# vs1003.net
KiCad netlist of a schematic drawn in Altium Designer
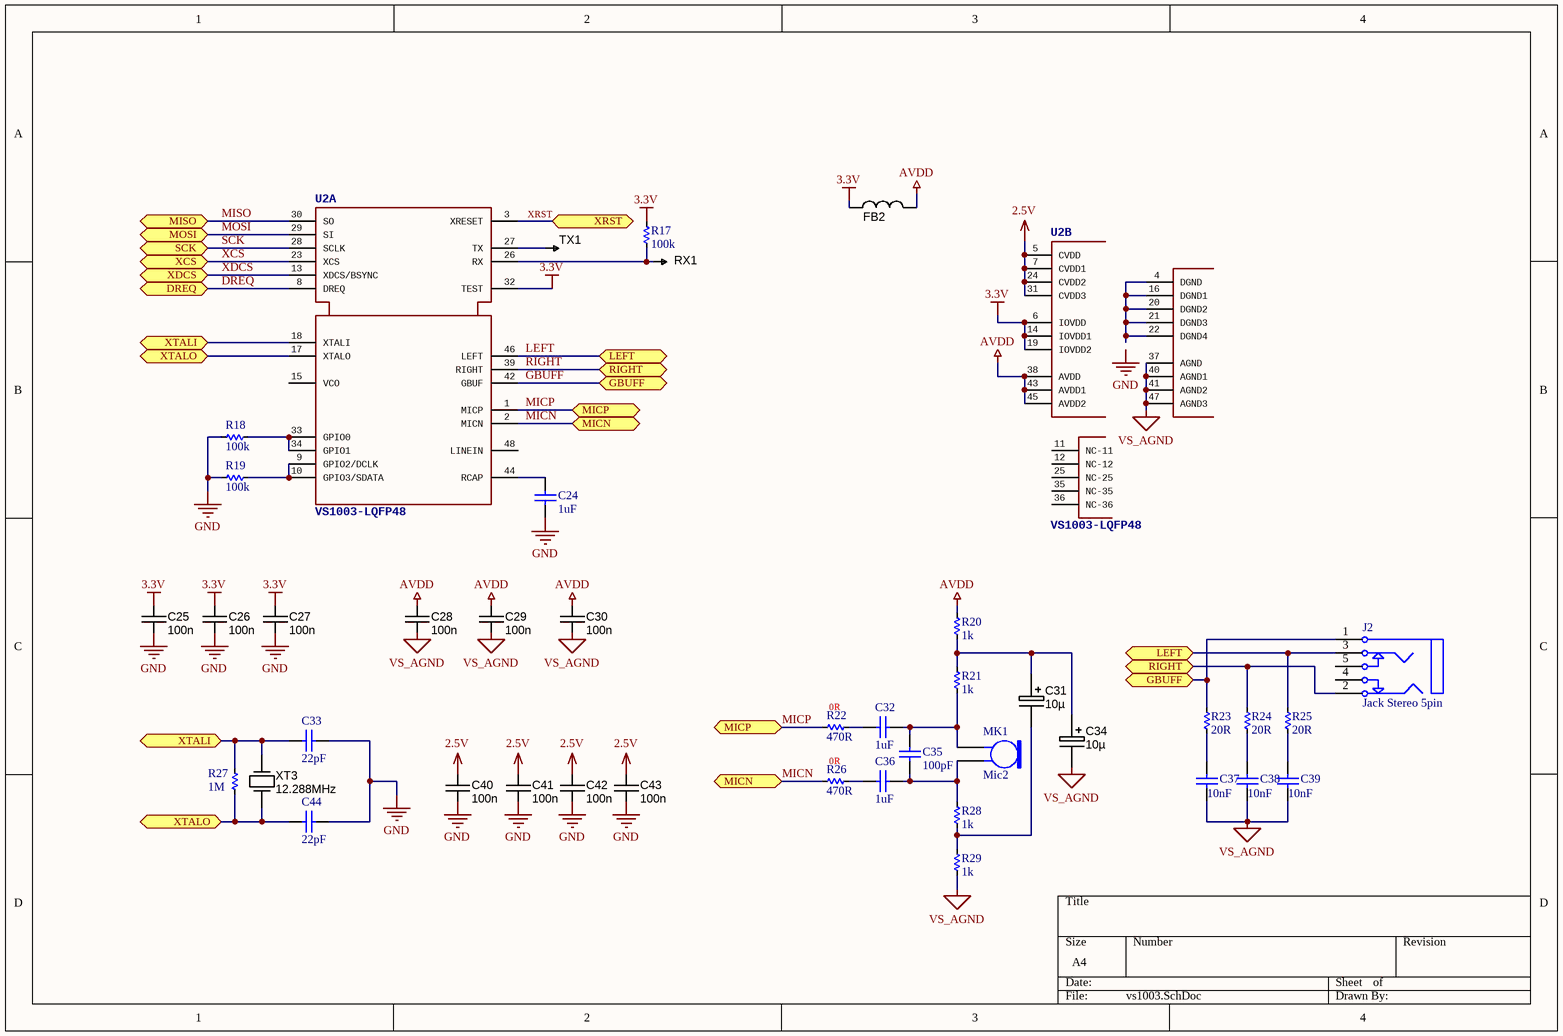
[diagram p0: vs1003.SchDoc]

(export (version "E")
  (design (tool "Eeschema 10.0.6"))
  (components
    (comp (ref "C24")
      (value "1uF")
      (footprint "C0805")
      (description "Capacitor (Semiconductor SIM Model)")
      (fields (field (name "Comment") "Cap Semi") (field (name "PUBLISHER") "Altium Limited"))
      (libsource (lib "Mylib") (part "Cap Semi"))
    )
    (comp (ref "C25")
      (value "100n")
      (footprint "CAPC1608X90N")
      (description "Capacitor SMD Cer 100nF 10% 50V X7R 0603")
      (fields (field (name "TOLERANCE") "±10%") (field (name "Comment") "approved sub OK"))
      (libsource (lib "PBL - Capacitors") (part "CAPC_100n_0603_X7R_50V_10%"))
    )
    (comp (ref "C26")
      (value "100n")
      (footprint "CAPC1608X90N")
      (description "Capacitor SMD Cer 100nF 10% 50V X7R 0603")
      (fields (field (name "TOLERANCE") "±10%") (field (name "Comment") "approved sub OK"))
      (libsource (lib "PBL - Capacitors") (part "CAPC_100n_0603_X7R_50V_10%"))
    )
    (comp (ref "C27")
      (value "100n")
      (footprint "CAPC1608X90N")
      (description "Capacitor SMD Cer 100nF 10% 50V X7R 0603")
      (fields (field (name "TOLERANCE") "±10%") (field (name "Comment") "approved sub OK"))
      (libsource (lib "PBL - Capacitors") (part "CAPC_100n_0603_X7R_50V_10%"))
    )
    (comp (ref "C28")
      (value "100n")
      (footprint "CAPC1608X90N")
      (description "Capacitor SMD Cer 100nF 10% 50V X7R 0603")
      (fields (field (name "TOLERANCE") "±10%") (field (name "Comment") "approved sub OK"))
      (libsource (lib "PBL - Capacitors") (part "CAPC_100n_0603_X7R_50V_10%"))
    )
    (comp (ref "C29")
      (value "100n")
      (footprint "CAPC1608X90N")
      (description "Capacitor SMD Cer 100nF 10% 50V X7R 0603")
      (fields (field (name "TOLERANCE") "±10%") (field (name "Comment") "approved sub OK"))
      (libsource (lib "PBL - Capacitors") (part "CAPC_100n_0603_X7R_50V_10%"))
    )
    (comp (ref "C30")
      (value "100n")
      (footprint "CAPC1608X90N")
      (description "Capacitor SMD Cer 100nF 10% 50V X7R 0603")
      (fields (field (name "TOLERANCE") "±10%") (field (name "Comment") "approved sub OK"))
      (libsource (lib "PBL - Capacitors") (part "CAPC_100n_0603_X7R_50V_10%"))
    )
    (comp (ref "C31")
      (value "10µ")
      (footprint "CAPMP3216X180N")
      (description "Capacitor SMD Tantalum 68uF 10% 6.3V EIA 3216-18")
      (fields (field (name "TOLERANCE") "±10%"))
      (libsource (lib "PBL - Capacitors") (part "CAPT_68u_3216_6V3"))
    )
    (comp (ref "C32")
      (value "1uF")
      (footprint "C0805")
      (description "Capacitor (Semiconductor SIM Model)")
      (fields (field (name "Comment") "Cap Semi") (field (name "PUBLISHER") "Altium Limited"))
      (libsource (lib "Mylib") (part "Cap Semi"))
    )
    (comp (ref "C33")
      (value "22pF")
      (footprint "C0805")
      (description "Capacitor (Semiconductor SIM Model)")
      (fields (field (name "Comment") "Cap Semi") (field (name "PUBLISHER") "Altium Limited"))
      (libsource (lib "Mylib") (part "Cap Semi"))
    )
    (comp (ref "C34")
      (value "10µ")
      (footprint "CAPMP3216X180N")
      (description "Capacitor SMD Tantalum 68uF 10% 6.3V EIA 3216-18")
      (fields (field (name "TOLERANCE") "±10%"))
      (libsource (lib "PBL - Capacitors") (part "CAPT_68u_3216_6V3"))
    )
    (comp (ref "C35")
      (value "100pF")
      (footprint "C0805")
      (description "Capacitor (Semiconductor SIM Model)")
      (fields (field (name "Comment") "Cap Semi") (field (name "PUBLISHER") "Altium Limited"))
      (libsource (lib "Mylib") (part "Cap Semi"))
    )
    (comp (ref "C36")
      (value "1uF")
      (footprint "C0805")
      (description "Capacitor (Semiconductor SIM Model)")
      (fields (field (name "Comment") "Cap Semi") (field (name "PUBLISHER") "Altium Limited"))
      (libsource (lib "Mylib") (part "Cap Semi"))
    )
    (comp (ref "C37")
      (value "10nF")
      (footprint "C0805")
      (description "Capacitor (Semiconductor SIM Model)")
      (fields (field (name "Comment") "Cap Semi") (field (name "PUBLISHER") "Altium Limited"))
      (libsource (lib "Mylib") (part "Cap Semi"))
    )
    (comp (ref "C38")
      (value "10nF")
      (footprint "C0805")
      (description "Capacitor (Semiconductor SIM Model)")
      (fields (field (name "Comment") "Cap Semi") (field (name "PUBLISHER") "Altium Limited"))
      (libsource (lib "Mylib") (part "Cap Semi"))
    )
    (comp (ref "C39")
      (value "10nF")
      (footprint "C0805")
      (description "Capacitor (Semiconductor SIM Model)")
      (fields (field (name "Comment") "Cap Semi") (field (name "PUBLISHER") "Altium Limited"))
      (libsource (lib "Mylib") (part "Cap Semi"))
    )
    (comp (ref "C40")
      (value "100n")
      (footprint "CAPC1608X90N")
      (description "Capacitor SMD Cer 100nF 10% 50V X7R 0603")
      (fields (field (name "TOLERANCE") "±10%") (field (name "Comment") "approved sub OK"))
      (libsource (lib "PBL - Capacitors") (part "CAPC_100n_0603_X7R_50V_10%"))
    )
    (comp (ref "C41")
      (value "100n")
      (footprint "CAPC1608X90N")
      (description "Capacitor SMD Cer 100nF 10% 50V X7R 0603")
      (fields (field (name "TOLERANCE") "±10%") (field (name "Comment") "approved sub OK"))
      (libsource (lib "PBL - Capacitors") (part "CAPC_100n_0603_X7R_50V_10%"))
    )
    (comp (ref "C42")
      (value "100n")
      (footprint "CAPC1608X90N")
      (description "Capacitor SMD Cer 100nF 10% 50V X7R 0603")
      (fields (field (name "TOLERANCE") "±10%") (field (name "Comment") "approved sub OK"))
      (libsource (lib "PBL - Capacitors") (part "CAPC_100n_0603_X7R_50V_10%"))
    )
    (comp (ref "C43")
      (value "100n")
      (footprint "CAPC1608X90N")
      (description "Capacitor SMD Cer 100nF 10% 50V X7R 0603")
      (fields (field (name "TOLERANCE") "±10%") (field (name "Comment") "approved sub OK"))
      (libsource (lib "PBL - Capacitors") (part "CAPC_100n_0603_X7R_50V_10%"))
    )
    (comp (ref "C44")
      (value "22pF")
      (footprint "C0805")
      (description "Capacitor (Semiconductor SIM Model)")
      (fields (field (name "Comment") "Cap Semi") (field (name "PUBLISHER") "Altium Limited"))
      (libsource (lib "Mylib") (part "Cap Semi"))
    )
    (comp (ref "FB2")
      (value "2K2 @ 100 MHz")
      (footprint "FBC2012N")
      (description "Ferrite bead 2.2K Ohm at 100 MHz 200mA 0805 SMD")
      (libsource (lib "PBL - Inductors") (part "FERRITE_2K2-100MHz_0805"))
    )
    (comp (ref "J2")
      (value "Jack Stereo 5pin")
      (footprint "Audio Jack 5 pin")
      (description "3-Conductor Jack with 2 break contacts (normals) and 2 auxiliary make contacts")
      (fields (field (name "PUBLISHER") "Altium Limited"))
      (libsource (lib "Mylib") (part "Jack Stereo 5pin"))
    )
    (comp (ref "MK1")
      (value "Mic2")
      (footprint "PIN2")
      (description "Microphone")
      (fields (field (name "PUBLISHER") "Altium Limited"))
      (libsource (lib "Miscellaneous Devices") (part "Mic2"))
    )
    (comp (ref "R17")
      (value "100k")
      (footprint "RES-SMD-0805")
      (description "Resistor")
      (fields
        (field (name "MANUFACTURER") "Generic Components")
        (field (name "Comment") "Res")
        (field (name "PUBLISHER") "Altium Hobart Technology Centre")
      )
      (libsource (lib "Mylib") (part "Res-SMD"))
    )
    (comp (ref "R18")
      (value "100k")
      (footprint "RES-SMD-0603")
      (description "Resistor")
      (fields
        (field (name "MANUFACTURER") "Generic Components")
        (field (name "Comment") "Res")
        (field (name "PUBLISHER") "Altium Hobart Technology Centre")
      )
      (libsource (lib "Mylib") (part "Res-SMD"))
    )
    (comp (ref "R19")
      (value "100k")
      (footprint "RES-SMD-0603")
      (description "Resistor")
      (fields
        (field (name "MANUFACTURER") "Generic Components")
        (field (name "Comment") "Res")
        (field (name "PUBLISHER") "Altium Hobart Technology Centre")
      )
      (libsource (lib "Mylib") (part "Res-SMD"))
    )
    (comp (ref "R20")
      (value "1k")
      (footprint "RES-SMD-0603")
      (description "Resistor")
      (fields
        (field (name "MANUFACTURER") "Generic Components")
        (field (name "Comment") "Res")
        (field (name "PUBLISHER") "Altium Hobart Technology Centre")
      )
      (libsource (lib "Mylib") (part "Res-SMD"))
    )
    (comp (ref "R21")
      (value "1k")
      (footprint "RES-SMD-0603")
      (description "Resistor")
      (fields
        (field (name "MANUFACTURER") "Generic Components")
        (field (name "Comment") "Res")
        (field (name "PUBLISHER") "Altium Hobart Technology Centre")
      )
      (libsource (lib "Mylib") (part "Res-SMD"))
    )
    (comp (ref "R22")
      (value "470R")
      (footprint "RES-SMD-0603")
      (description "Resistor")
      (fields
        (field (name "MANUFACTURER") "Generic Components")
        (field (name "Comment") "Res")
        (field (name "PUBLISHER") "Altium Hobart Technology Centre")
      )
      (libsource (lib "Mylib") (part "Res-SMD"))
    )
    (comp (ref "R23")
      (value "20R")
      (footprint "RES-SMD-0805")
      (description "Resistor")
      (fields
        (field (name "MANUFACTURER") "Generic Components")
        (field (name "Comment") "Res")
        (field (name "PUBLISHER") "Altium Hobart Technology Centre")
      )
      (libsource (lib "Mylib") (part "Res-SMD"))
    )
    (comp (ref "R24")
      (value "20R")
      (footprint "RES-SMD-0805")
      (description "Resistor")
      (fields
        (field (name "MANUFACTURER") "Generic Components")
        (field (name "Comment") "Res")
        (field (name "PUBLISHER") "Altium Hobart Technology Centre")
      )
      (libsource (lib "Mylib") (part "Res-SMD"))
    )
    (comp (ref "R25")
      (value "20R")
      (footprint "RES-SMD-0805")
      (description "Resistor")
      (fields
        (field (name "MANUFACTURER") "Generic Components")
        (field (name "Comment") "Res")
        (field (name "PUBLISHER") "Altium Hobart Technology Centre")
      )
      (libsource (lib "Mylib") (part "Res-SMD"))
    )
    (comp (ref "R26")
      (value "470R")
      (footprint "RES-SMD-0603")
      (description "Resistor")
      (fields
        (field (name "MANUFACTURER") "Generic Components")
        (field (name "Comment") "Res")
        (field (name "PUBLISHER") "Altium Hobart Technology Centre")
      )
      (libsource (lib "Mylib") (part "Res-SMD"))
    )
    (comp (ref "R27")
      (value "1M")
      (footprint "RES-SMD-0805")
      (description "Resistor")
      (fields
        (field (name "MANUFACTURER") "Generic Components")
        (field (name "Comment") "Res")
        (field (name "PUBLISHER") "Altium Hobart Technology Centre")
      )
      (libsource (lib "Mylib") (part "Res-SMD"))
    )
    (comp (ref "R28")
      (value "1k")
      (footprint "RES-SMD-0603")
      (description "Resistor")
      (fields
        (field (name "MANUFACTURER") "Generic Components")
        (field (name "Comment") "Res")
        (field (name "PUBLISHER") "Altium Hobart Technology Centre")
      )
      (libsource (lib "Mylib") (part "Res-SMD"))
    )
    (comp (ref "R29")
      (value "1k")
      (footprint "RES-SMD-0603")
      (description "Resistor")
      (fields
        (field (name "MANUFACTURER") "Generic Components")
        (field (name "Comment") "Res")
        (field (name "PUBLISHER") "Altium Hobart Technology Centre")
      )
      (libsource (lib "Mylib") (part "Res-SMD"))
    )
    (comp (ref "RX1")
      (value "TESTPOINT")
      (footprint "TP-R60")
      (description "SMD test pin")
      (libsource (lib "PBL - Test Points") (part "TESTPOINT"))
    )
    (comp (ref "TX1")
      (value "TESTPOINT")
      (footprint "TP-R60")
      (description "SMD test pin")
      (libsource (lib "PBL - Test Points") (part "TESTPOINT"))
    )
    (comp (ref "U2")
      (value "VS1003-LQFP48")
      (footprint "LQFP48")
      (description "MP3/WMA Audio Codec   http://www.vlsi.fi/fileadmin/datasheets/vlsi/vs1003.pdf")
      (libsource (lib "Mylib") (part "VS1003-LQFP48"))
    )
    (comp (ref "XT3")
      (value "12.288MHz")
      (footprint "CRYSTAL_HC49-US-SM")
      (description "Resonator Ceramic 6.00 MHz 30ppm")
      (libsource (lib "PBL - Resonators") (part "Crystal_6MHz_HC49/US"))
    )
  )
  (nets
    (net (code "1") (name "/DREQ") (class "Default")
      (node (ref "U2") (pin "8") (pinfunction "DREQ_8") (pintype "passive"))
    )
    (net (code "2") (name "/GBUFF") (class "Default")
      (node (ref "J2") (pin "1") (pinfunction "1_1") (pintype "passive"))
      (node (ref "R23") (pin "1") (pinfunction "1_1") (pintype "passive"))
      (node (ref "U2") (pin "42") (pinfunction "GBUF_42") (pintype "passive"))
    )
    (net (code "3") (name "/LEFT") (class "Default")
      (node (ref "J2") (pin "3") (pinfunction "3_3") (pintype "passive"))
      (node (ref "R25") (pin "1") (pinfunction "1_1") (pintype "passive"))
      (node (ref "U2") (pin "46") (pinfunction "LEFT_46") (pintype "passive"))
    )
    (net (code "4") (name "/MICN") (class "Default")
      (node (ref "R26") (pin "2") (pinfunction "2_2") (pintype "passive"))
      (node (ref "U2") (pin "2") (pinfunction "MICN_2") (pintype "passive"))
    )
    (net (code "5") (name "/MICP") (class "Default")
      (node (ref "R22") (pin "2") (pinfunction "2_2") (pintype "passive"))
      (node (ref "U2") (pin "1") (pinfunction "MICP_1") (pintype "passive"))
    )
    (net (code "6") (name "/MISO") (class "Default")
      (node (ref "U2") (pin "30") (pinfunction "SO_30") (pintype "passive"))
    )
    (net (code "7") (name "/MOSI") (class "Default")
      (node (ref "U2") (pin "29") (pinfunction "SI_29") (pintype "passive"))
    )
    (net (code "8") (name "/RIGHT") (class "Default")
      (node (ref "J2") (pin "2") (pinfunction "2_2") (pintype "passive"))
      (node (ref "R24") (pin "1") (pinfunction "1_1") (pintype "passive"))
      (node (ref "U2") (pin "39") (pinfunction "RIGHT_39") (pintype "passive"))
    )
    (net (code "9") (name "/SCK") (class "Default")
      (node (ref "U2") (pin "28") (pinfunction "SCLK_28") (pintype "passive"))
    )
    (net (code "10") (name "/XCS") (class "Default")
      (node (ref "U2") (pin "23") (pinfunction "XCS_23") (pintype "passive"))
    )
    (net (code "11") (name "/XDCS") (class "Default")
      (node (ref "U2") (pin "13") (pinfunction "XDCS/BSYNC_13") (pintype "passive"))
    )
    (net (code "12") (name "/XRST") (class "Default")
      (node (ref "U2") (pin "3") (pinfunction "XRESET_3") (pintype "passive"))
    )
    (net (code "13") (name "/XTALI") (class "Default")
      (node (ref "C33") (pin "2") (pinfunction "2_2") (pintype "passive"))
      (node (ref "R27") (pin "1") (pinfunction "1_1") (pintype "passive"))
      (node (ref "U2") (pin "18") (pinfunction "XTALI_18") (pintype "passive"))
      (node (ref "XT3") (pin "2") (pinfunction "OUT_2") (pintype "passive"))
    )
    (net (code "14") (name "/XTALO") (class "Default")
      (node (ref "C44") (pin "2") (pinfunction "2_2") (pintype "passive"))
      (node (ref "R27") (pin "2") (pinfunction "2_2") (pintype "passive"))
      (node (ref "U2") (pin "17") (pinfunction "XTALO_17") (pintype "passive"))
      (node (ref "XT3") (pin "1") (pinfunction "IN_1") (pintype "passive"))
    )
    (net (code "15") (name "2.5V") (class "Default")
      (node (ref "C40") (pin "1") (pintype "passive"))
      (node (ref "C41") (pin "1") (pintype "passive"))
      (node (ref "C42") (pin "1") (pintype "passive"))
      (node (ref "C43") (pin "1") (pintype "passive"))
      (node (ref "U2") (pin "24") (pinfunction "CVDD2_24") (pintype "power_in"))
      (node (ref "U2") (pin "31") (pinfunction "CVDD3_31") (pintype "power_in"))
      (node (ref "U2") (pin "5") (pinfunction "CVDD_5") (pintype "power_in"))
      (node (ref "U2") (pin "7") (pinfunction "CVDD1_7") (pintype "power_in"))
    )
    (net (code "16") (name "3.3V") (class "Default")
      (node (ref "C25") (pin "1") (pintype "passive"))
      (node (ref "C26") (pin "1") (pintype "passive"))
      (node (ref "C27") (pin "1") (pintype "passive"))
      (node (ref "FB2") (pin "1") (pinfunction "1_1") (pintype "passive"))
      (node (ref "R17") (pin "1") (pinfunction "1_1") (pintype "passive"))
      (node (ref "U2") (pin "14") (pinfunction "IOVDD1_14") (pintype "power_in"))
      (node (ref "U2") (pin "19") (pinfunction "IOVDD2_19") (pintype "power_in"))
      (node (ref "U2") (pin "32") (pinfunction "TEST_32") (pintype "passive"))
      (node (ref "U2") (pin "6") (pinfunction "IOVDD_6") (pintype "power_in"))
    )
    (net (code "17") (name "AVDD") (class "Default")
      (node (ref "C28") (pin "1") (pintype "passive"))
      (node (ref "C29") (pin "1") (pintype "passive"))
      (node (ref "C30") (pin "1") (pintype "passive"))
      (node (ref "FB2") (pin "2") (pinfunction "2_2") (pintype "passive"))
      (node (ref "R20") (pin "1") (pinfunction "1_1") (pintype "passive"))
      (node (ref "U2") (pin "38") (pinfunction "AVDD_38") (pintype "power_in"))
      (node (ref "U2") (pin "43") (pinfunction "AVDD1_43") (pintype "power_in"))
      (node (ref "U2") (pin "45") (pinfunction "AVDD2_45") (pintype "power_in"))
    )
    (net (code "18") (name "GND") (class "Default")
      (node (ref "C24") (pin "1") (pinfunction "1_1") (pintype "passive"))
      (node (ref "C25") (pin "2") (pintype "passive"))
      (node (ref "C26") (pin "2") (pintype "passive"))
      (node (ref "C27") (pin "2") (pintype "passive"))
      (node (ref "C33") (pin "1") (pinfunction "1_1") (pintype "passive"))
      (node (ref "C40") (pin "2") (pintype "passive"))
      (node (ref "C41") (pin "2") (pintype "passive"))
      (node (ref "C42") (pin "2") (pintype "passive"))
      (node (ref "C43") (pin "2") (pintype "passive"))
      (node (ref "C44") (pin "1") (pinfunction "1_1") (pintype "passive"))
      (node (ref "R18") (pin "1") (pinfunction "1_1") (pintype "passive"))
      (node (ref "R19") (pin "1") (pinfunction "1_1") (pintype "passive"))
    )
    (net (code "19") (name "Net-(C31-Pad1)") (class "Default")
      (node (ref "C31") (pin "1") (pintype "passive"))
      (node (ref "C34") (pin "1") (pintype "passive"))
      (node (ref "R20") (pin "2") (pinfunction "2_2") (pintype "passive"))
      (node (ref "R21") (pin "1") (pinfunction "1_1") (pintype "passive"))
    )
    (net (code "20") (name "Net-(C31-Pad2)") (class "Default")
      (node (ref "C31") (pin "2") (pintype "passive"))
      (node (ref "R28") (pin "2") (pinfunction "2_2") (pintype "passive"))
      (node (ref "R29") (pin "1") (pinfunction "1_1") (pintype "passive"))
    )
    (net (code "21") (name "Net-(C32-Pad1)") (class "Default")
      (node (ref "C32") (pin "1") (pinfunction "1_1") (pintype "passive"))
      (node (ref "R22") (pin "1") (pinfunction "1_1") (pintype "passive"))
    )
    (net (code "22") (name "Net-(C32-Pad2)") (class "Default")
      (node (ref "C32") (pin "2") (pinfunction "2_2") (pintype "passive"))
      (node (ref "C35") (pin "2") (pinfunction "2_2") (pintype "passive"))
      (node (ref "MK1") (pin "1") (pinfunction "1_1") (pintype "passive"))
      (node (ref "R21") (pin "2") (pinfunction "2_2") (pintype "passive"))
    )
    (net (code "23") (name "Net-(C35-Pad1)") (class "Default")
      (node (ref "C35") (pin "1") (pinfunction "1_1") (pintype "passive"))
      (node (ref "C36") (pin "2") (pinfunction "2_2") (pintype "passive"))
      (node (ref "MK1") (pin "2") (pinfunction "2_2") (pintype "passive"))
      (node (ref "R28") (pin "1") (pinfunction "1_1") (pintype "passive"))
    )
    (net (code "24") (name "Net-(C36-Pad1)") (class "Default")
      (node (ref "C36") (pin "1") (pinfunction "1_1") (pintype "passive"))
      (node (ref "R26") (pin "1") (pinfunction "1_1") (pintype "passive"))
    )
    (net (code "25") (name "Net-(C37-Pad2)") (class "Default")
      (node (ref "C37") (pin "2") (pinfunction "2_2") (pintype "passive"))
      (node (ref "R23") (pin "2") (pinfunction "2_2") (pintype "passive"))
    )
    (net (code "26") (name "Net-(C38-Pad2)") (class "Default")
      (node (ref "C38") (pin "2") (pinfunction "2_2") (pintype "passive"))
      (node (ref "R24") (pin "2") (pinfunction "2_2") (pintype "passive"))
    )
    (net (code "27") (name "Net-(C39-Pad2)") (class "Default")
      (node (ref "C39") (pin "2") (pinfunction "2_2") (pintype "passive"))
      (node (ref "R25") (pin "2") (pinfunction "2_2") (pintype "passive"))
    )
    (net (code "28") (name "Net-(U2A-GPIO0)") (class "Default")
      (node (ref "R18") (pin "2") (pinfunction "2_2") (pintype "passive"))
      (node (ref "U2") (pin "33") (pinfunction "GPIO0_33") (pintype "passive"))
      (node (ref "U2") (pin "34") (pinfunction "GPIO1_34") (pintype "passive"))
    )
    (net (code "29") (name "Net-(U2A-GPIO2{slash}DCLK)") (class "Default")
      (node (ref "R19") (pin "2") (pinfunction "2_2") (pintype "passive"))
      (node (ref "U2") (pin "10") (pinfunction "GPIO3/SDATA_10") (pintype "passive"))
      (node (ref "U2") (pin "9") (pinfunction "GPIO2/DCLK_9") (pintype "passive"))
    )
    (net (code "30") (name "Net-(U2A-RCAP)") (class "Default")
      (node (ref "C24") (pin "2") (pinfunction "2_2") (pintype "passive"))
      (node (ref "U2") (pin "44") (pinfunction "RCAP_44") (pintype "passive"))
    )
    (net (code "31") (name "Net-(U2A-RX)") (class "Default")
      (node (ref "R17") (pin "2") (pinfunction "2_2") (pintype "passive"))
      (node (ref "RX1") (pin "1") (pintype "passive"))
      (node (ref "U2") (pin "26") (pinfunction "RX_26") (pintype "passive"))
    )
    (net (code "32") (name "Net-(U2A-TX)") (class "Default")
      (node (ref "TX1") (pin "1") (pintype "passive"))
      (node (ref "U2") (pin "27") (pinfunction "TX_27") (pintype "passive"))
    )
    (net (code "33") (name "Net-(U2B-DGND)") (class "Default")
      (node (ref "U2") (pin "16") (pinfunction "DGND1_16") (pintype "open_emitter"))
      (node (ref "U2") (pin "20") (pinfunction "DGND2_20") (pintype "open_emitter"))
      (node (ref "U2") (pin "21") (pinfunction "DGND3_21") (pintype "open_emitter"))
      (node (ref "U2") (pin "22") (pinfunction "DGND4_22") (pintype "open_emitter"))
      (node (ref "U2") (pin "4") (pinfunction "DGND_4") (pintype "open_emitter"))
    )
    (net (code "34") (name "VS_AGND") (class "Default")
      (node (ref "C28") (pin "2") (pintype "passive"))
      (node (ref "C29") (pin "2") (pintype "passive"))
      (node (ref "C30") (pin "2") (pintype "passive"))
      (node (ref "C34") (pin "2") (pintype "passive"))
      (node (ref "C37") (pin "1") (pinfunction "1_1") (pintype "passive"))
      (node (ref "C38") (pin "1") (pinfunction "1_1") (pintype "passive"))
      (node (ref "C39") (pin "1") (pinfunction "1_1") (pintype "passive"))
      (node (ref "R29") (pin "2") (pinfunction "2_2") (pintype "passive"))
      (node (ref "U2") (pin "37") (pinfunction "AGND_37") (pintype "open_emitter"))
      (node (ref "U2") (pin "40") (pinfunction "AGND1_40") (pintype "open_emitter"))
      (node (ref "U2") (pin "41") (pinfunction "AGND2_41") (pintype "open_emitter"))
      (node (ref "U2") (pin "47") (pinfunction "AGND3_47") (pintype "open_emitter"))
    )
    (net (code "35") (name "unconnected-(J2-Pad4)") (class "Default")
      (node (ref "J2") (pin "4") (pinfunction "4_4") (pintype "passive"))
    )
    (net (code "36") (name "unconnected-(J2-Pad5)") (class "Default")
      (node (ref "J2") (pin "5") (pinfunction "5_5") (pintype "passive"))
    )
    (net (code "37") (name "unconnected-(U2A-LINEIN-Pad48)") (class "Default")
      (node (ref "U2") (pin "48") (pinfunction "LINEIN_48") (pintype "passive"))
    )
    (net (code "38") (name "unconnected-(U2A-VCO-Pad15)") (class "Default")
      (node (ref "U2") (pin "15") (pinfunction "VCO_15") (pintype "passive"))
    )
    (net (code "39") (name "unconnected-(U2B-NC-11-Pad11)") (class "Default")
      (node (ref "U2") (pin "11") (pinfunction "NC-11_11") (pintype "passive"))
    )
    (net (code "40") (name "unconnected-(U2B-NC-12-Pad12)") (class "Default")
      (node (ref "U2") (pin "12") (pinfunction "NC-12_12") (pintype "passive"))
    )
    (net (code "41") (name "unconnected-(U2B-NC-25-Pad25)") (class "Default")
      (node (ref "U2") (pin "25") (pinfunction "NC-25_25") (pintype "passive"))
    )
    (net (code "42") (name "unconnected-(U2B-NC-35-Pad35)") (class "Default")
      (node (ref "U2") (pin "35") (pinfunction "NC-35_35") (pintype "passive"))
    )
    (net (code "43") (name "unconnected-(U2B-NC-36-Pad36)") (class "Default")
      (node (ref "U2") (pin "36") (pinfunction "NC-36_36") (pintype "passive"))
    )
  )
)
